# brain2_v12.net
KiCad netlist of a schematic drawn in EAGLE
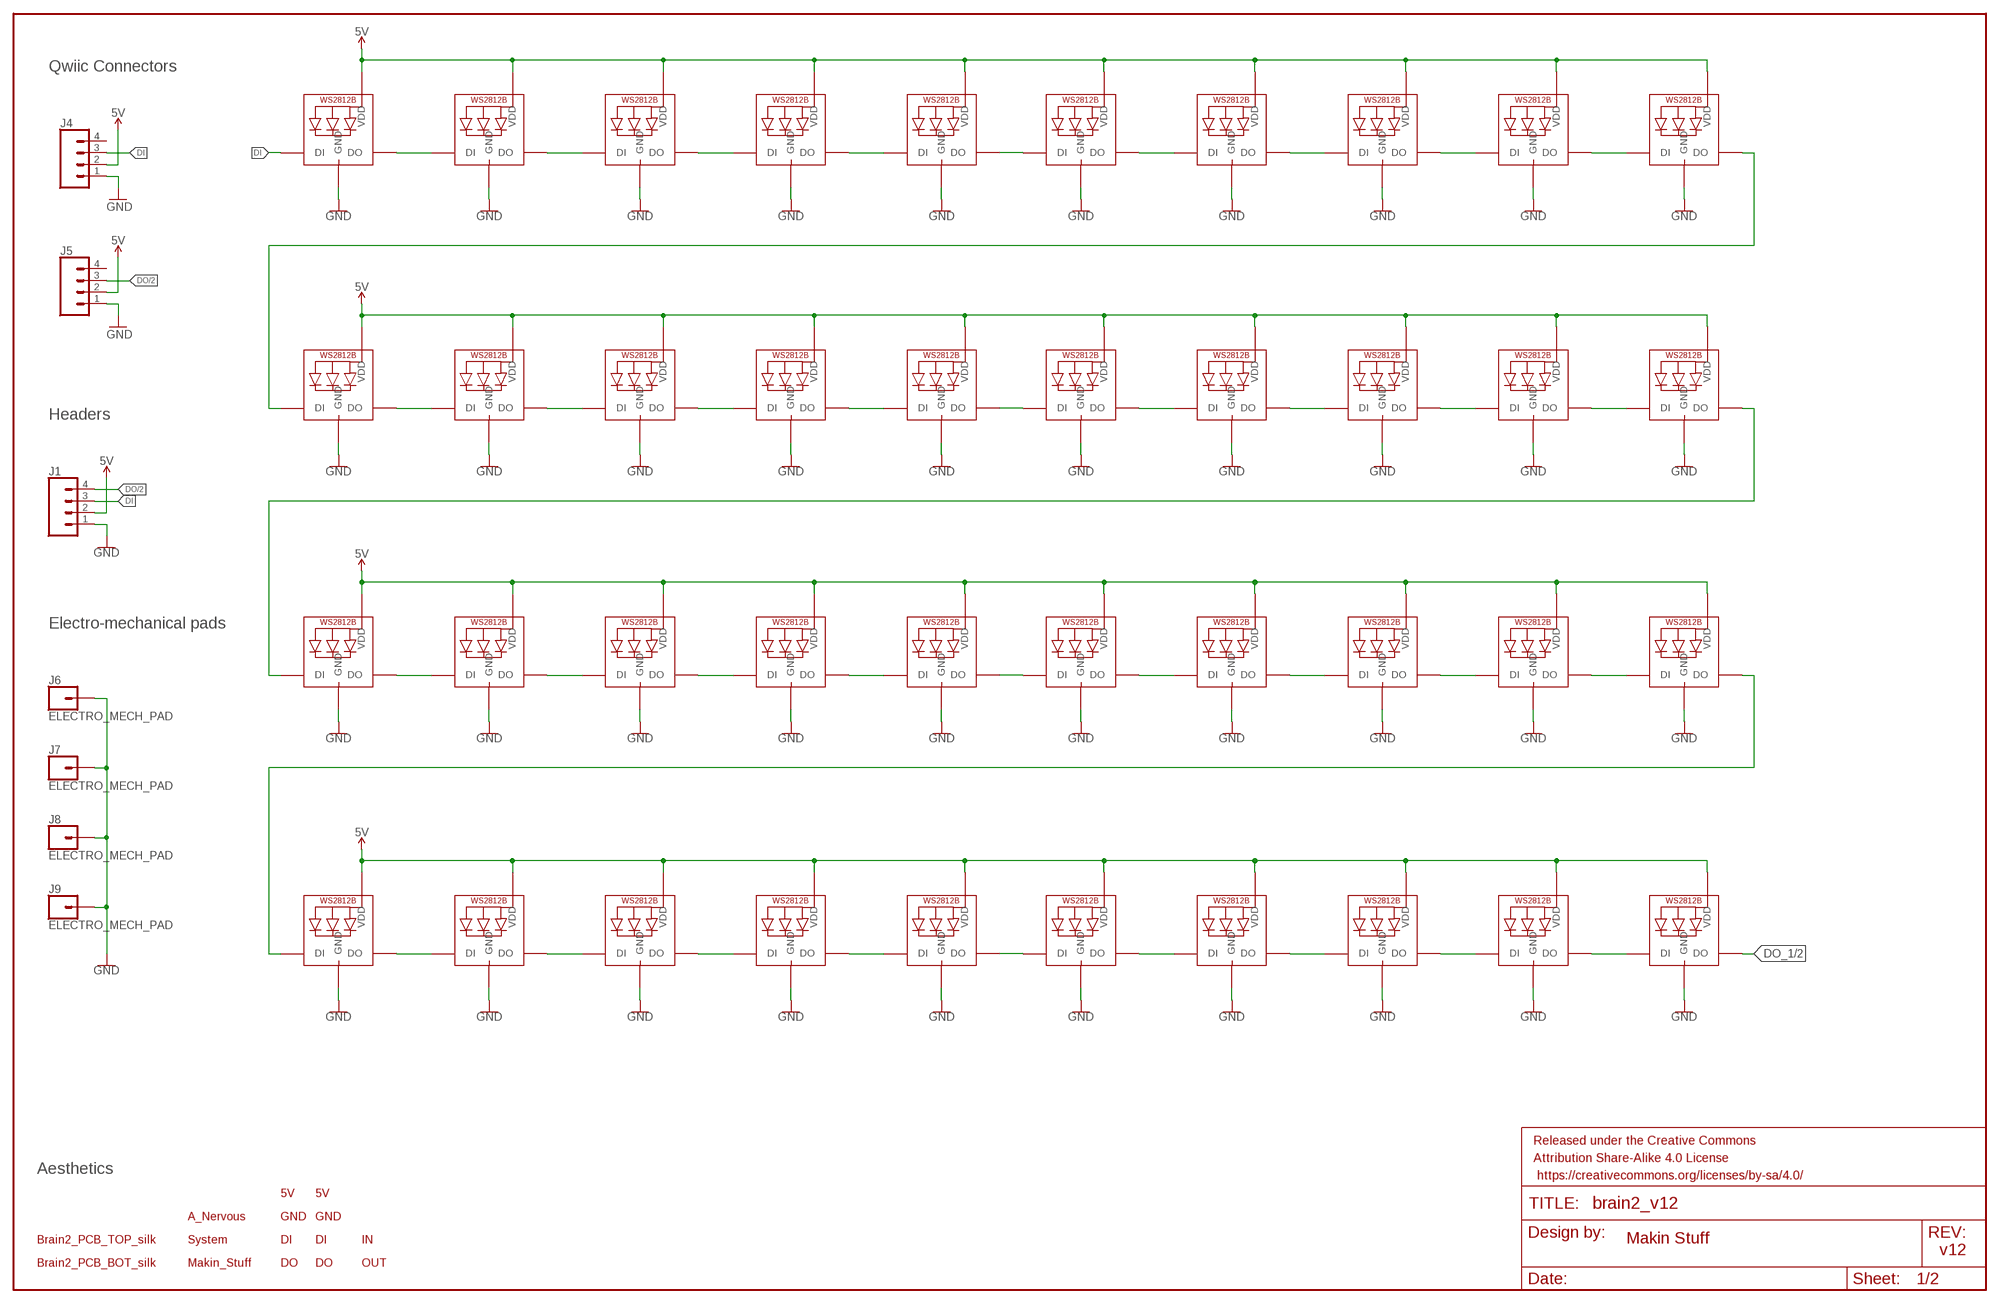
[diagram p0: schematic, sheet 1]
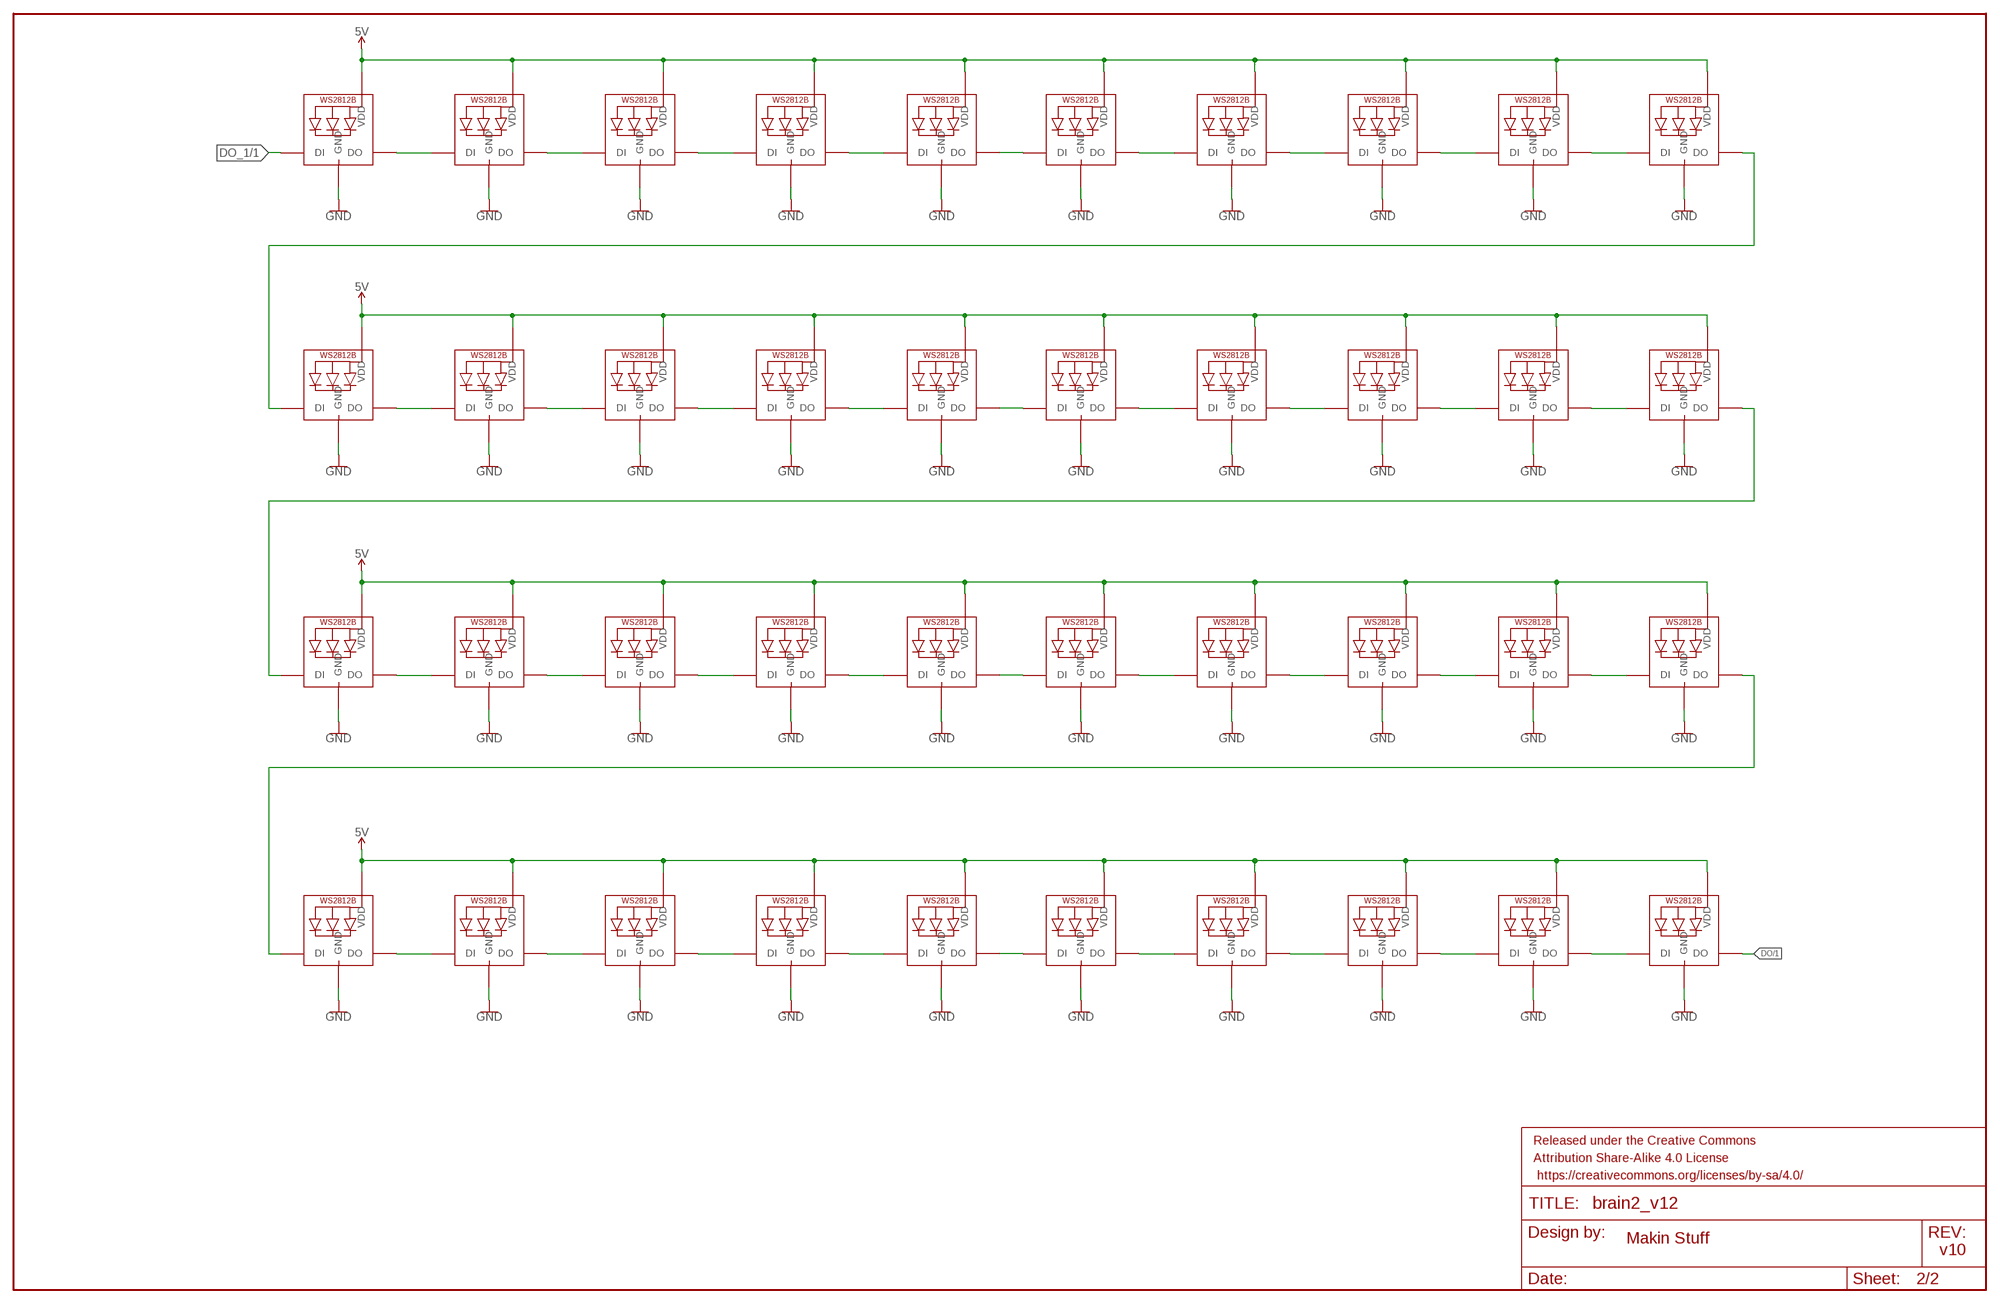
[diagram p1: schematic, sheet 2]

(export (version "E")
  (design (tool "Eeschema 10.0.6"))
  (components
    (comp (ref "FRAME2")
      (value "FRAME-LEDGER")
      (footprint "eagle-import:CREATIVE_COMMONS")
      (libsource (lib "eagle-import") (part "FRAME-LEDGER"))
    )
    (comp (ref "J1")
      (value "CONN_041X04_NO_SILK_NO_POP")
      (footprint "eagle-import:1X04_NO_SILK")
      (libsource (lib "eagle-import") (part "CONN_041X04_NO_SILK_NO_POP"))
    )
    (comp (ref "J4")
      (value "CONN_04SMD3")
      (footprint "eagle-import:JST04_1MM_RA")
      (libsource (lib "eagle-import") (part "CONN_04SMD3"))
    )
    (comp (ref "J5")
      (value "CONN_04SMD3")
      (footprint "eagle-import:JST04_1MM_RA")
      (libsource (lib "eagle-import") (part "CONN_04SMD3"))
    )
    (comp (ref "J6")
      (value "ELECTRO_MECH_PAD")
      (footprint "eagle-import:5X3_SOLDER_PAD")
      (libsource (lib "eagle-import") (part "ELECTRO_MECH_PAD"))
    )
    (comp (ref "J7")
      (value "ELECTRO_MECH_PAD")
      (footprint "eagle-import:5X3_SOLDER_PAD")
      (libsource (lib "eagle-import") (part "ELECTRO_MECH_PAD"))
    )
    (comp (ref "J8")
      (value "ELECTRO_MECH_PAD")
      (footprint "eagle-import:5X3_SOLDER_PAD")
      (libsource (lib "eagle-import") (part "ELECTRO_MECH_PAD"))
    )
    (comp (ref "J9")
      (value "ELECTRO_MECH_PAD")
      (footprint "eagle-import:5X3_SOLDER_PAD")
      (libsource (lib "eagle-import") (part "ELECTRO_MECH_PAD"))
    )
    (comp (ref "LED1")
      (value "3.5X3.5_RGB_LED3.5X3.5")
      (footprint "eagle-import:3.5X3.5_RGB_LED")
      (libsource (lib "eagle-import") (part "3.5X3.5_RGB_LED3.5X3.5"))
    )
    (comp (ref "LED2")
      (value "3.5X3.5_RGB_LED3.5X3.5")
      (footprint "eagle-import:3.5X3.5_RGB_LED")
      (libsource (lib "eagle-import") (part "3.5X3.5_RGB_LED3.5X3.5"))
    )
    (comp (ref "LED3")
      (value "3.5X3.5_RGB_LED3.5X3.5")
      (footprint "eagle-import:3.5X3.5_RGB_LED")
      (libsource (lib "eagle-import") (part "3.5X3.5_RGB_LED3.5X3.5"))
    )
    (comp (ref "LED4")
      (value "3.5X3.5_RGB_LED3.5X3.5")
      (footprint "eagle-import:3.5X3.5_RGB_LED")
      (libsource (lib "eagle-import") (part "3.5X3.5_RGB_LED3.5X3.5"))
    )
    (comp (ref "LED5")
      (value "3.5X3.5_RGB_LED3.5X3.5")
      (footprint "eagle-import:3.5X3.5_RGB_LED")
      (libsource (lib "eagle-import") (part "3.5X3.5_RGB_LED3.5X3.5"))
    )
    (comp (ref "LED6")
      (value "3.5X3.5_RGB_LED3.5X3.5")
      (footprint "eagle-import:3.5X3.5_RGB_LED")
      (libsource (lib "eagle-import") (part "3.5X3.5_RGB_LED3.5X3.5"))
    )
    (comp (ref "LED7")
      (value "3.5X3.5_RGB_LED3.5X3.5")
      (footprint "eagle-import:3.5X3.5_RGB_LED")
      (libsource (lib "eagle-import") (part "3.5X3.5_RGB_LED3.5X3.5"))
    )
    (comp (ref "LED8")
      (value "3.5X3.5_RGB_LED3.5X3.5")
      (footprint "eagle-import:3.5X3.5_RGB_LED")
      (libsource (lib "eagle-import") (part "3.5X3.5_RGB_LED3.5X3.5"))
    )
    (comp (ref "LED9")
      (value "3.5X3.5_RGB_LED3.5X3.5")
      (footprint "eagle-import:3.5X3.5_RGB_LED")
      (libsource (lib "eagle-import") (part "3.5X3.5_RGB_LED3.5X3.5"))
    )
    (comp (ref "LED10")
      (value "3.5X3.5_RGB_LED3.5X3.5")
      (footprint "eagle-import:3.5X3.5_RGB_LED")
      (libsource (lib "eagle-import") (part "3.5X3.5_RGB_LED3.5X3.5"))
    )
    (comp (ref "LED11")
      (value "3.5X3.5_RGB_LED3.5X3.5")
      (footprint "eagle-import:3.5X3.5_RGB_LED")
      (libsource (lib "eagle-import") (part "3.5X3.5_RGB_LED3.5X3.5"))
    )
    (comp (ref "LED12")
      (value "3.5X3.5_RGB_LED3.5X3.5")
      (footprint "eagle-import:3.5X3.5_RGB_LED")
      (libsource (lib "eagle-import") (part "3.5X3.5_RGB_LED3.5X3.5"))
    )
    (comp (ref "LED13")
      (value "3.5X3.5_RGB_LED3.5X3.5")
      (footprint "eagle-import:3.5X3.5_RGB_LED")
      (libsource (lib "eagle-import") (part "3.5X3.5_RGB_LED3.5X3.5"))
    )
    (comp (ref "LED14")
      (value "3.5X3.5_RGB_LED3.5X3.5")
      (footprint "eagle-import:3.5X3.5_RGB_LED")
      (libsource (lib "eagle-import") (part "3.5X3.5_RGB_LED3.5X3.5"))
    )
    (comp (ref "LED15")
      (value "3.5X3.5_RGB_LED3.5X3.5")
      (footprint "eagle-import:3.5X3.5_RGB_LED")
      (libsource (lib "eagle-import") (part "3.5X3.5_RGB_LED3.5X3.5"))
    )
    (comp (ref "LED16")
      (value "3.5X3.5_RGB_LED3.5X3.5")
      (footprint "eagle-import:3.5X3.5_RGB_LED")
      (libsource (lib "eagle-import") (part "3.5X3.5_RGB_LED3.5X3.5"))
    )
    (comp (ref "LED17")
      (value "3.5X3.5_RGB_LED3.5X3.5")
      (footprint "eagle-import:3.5X3.5_RGB_LED")
      (libsource (lib "eagle-import") (part "3.5X3.5_RGB_LED3.5X3.5"))
    )
    (comp (ref "LED18")
      (value "3.5X3.5_RGB_LED3.5X3.5")
      (footprint "eagle-import:3.5X3.5_RGB_LED")
      (libsource (lib "eagle-import") (part "3.5X3.5_RGB_LED3.5X3.5"))
    )
    (comp (ref "LED19")
      (value "3.5X3.5_RGB_LED3.5X3.5")
      (footprint "eagle-import:3.5X3.5_RGB_LED")
      (libsource (lib "eagle-import") (part "3.5X3.5_RGB_LED3.5X3.5"))
    )
    (comp (ref "LED20")
      (value "3.5X3.5_RGB_LED3.5X3.5")
      (footprint "eagle-import:3.5X3.5_RGB_LED")
      (libsource (lib "eagle-import") (part "3.5X3.5_RGB_LED3.5X3.5"))
    )
    (comp (ref "LED21")
      (value "3.5X3.5_RGB_LED3.5X3.5")
      (footprint "eagle-import:3.5X3.5_RGB_LED")
      (libsource (lib "eagle-import") (part "3.5X3.5_RGB_LED3.5X3.5"))
    )
    (comp (ref "LED22")
      (value "3.5X3.5_RGB_LED3.5X3.5")
      (footprint "eagle-import:3.5X3.5_RGB_LED")
      (libsource (lib "eagle-import") (part "3.5X3.5_RGB_LED3.5X3.5"))
    )
    (comp (ref "LED23")
      (value "3.5X3.5_RGB_LED3.5X3.5")
      (footprint "eagle-import:3.5X3.5_RGB_LED")
      (libsource (lib "eagle-import") (part "3.5X3.5_RGB_LED3.5X3.5"))
    )
    (comp (ref "LED24")
      (value "3.5X3.5_RGB_LED3.5X3.5")
      (footprint "eagle-import:3.5X3.5_RGB_LED")
      (libsource (lib "eagle-import") (part "3.5X3.5_RGB_LED3.5X3.5"))
    )
    (comp (ref "LED25")
      (value "3.5X3.5_RGB_LED3.5X3.5")
      (footprint "eagle-import:3.5X3.5_RGB_LED")
      (libsource (lib "eagle-import") (part "3.5X3.5_RGB_LED3.5X3.5"))
    )
    (comp (ref "LED26")
      (value "3.5X3.5_RGB_LED3.5X3.5")
      (footprint "eagle-import:3.5X3.5_RGB_LED")
      (libsource (lib "eagle-import") (part "3.5X3.5_RGB_LED3.5X3.5"))
    )
    (comp (ref "LED27")
      (value "3.5X3.5_RGB_LED3.5X3.5")
      (footprint "eagle-import:3.5X3.5_RGB_LED")
      (libsource (lib "eagle-import") (part "3.5X3.5_RGB_LED3.5X3.5"))
    )
    (comp (ref "LED28")
      (value "3.5X3.5_RGB_LED3.5X3.5")
      (footprint "eagle-import:3.5X3.5_RGB_LED")
      (libsource (lib "eagle-import") (part "3.5X3.5_RGB_LED3.5X3.5"))
    )
    (comp (ref "LED29")
      (value "3.5X3.5_RGB_LED3.5X3.5")
      (footprint "eagle-import:3.5X3.5_RGB_LED")
      (libsource (lib "eagle-import") (part "3.5X3.5_RGB_LED3.5X3.5"))
    )
    (comp (ref "LED30")
      (value "3.5X3.5_RGB_LED3.5X3.5")
      (footprint "eagle-import:3.5X3.5_RGB_LED")
      (libsource (lib "eagle-import") (part "3.5X3.5_RGB_LED3.5X3.5"))
    )
    (comp (ref "LED31")
      (value "3.5X3.5_RGB_LED3.5X3.5")
      (footprint "eagle-import:3.5X3.5_RGB_LED")
      (libsource (lib "eagle-import") (part "3.5X3.5_RGB_LED3.5X3.5"))
    )
    (comp (ref "LED32")
      (value "3.5X3.5_RGB_LED3.5X3.5")
      (footprint "eagle-import:3.5X3.5_RGB_LED")
      (libsource (lib "eagle-import") (part "3.5X3.5_RGB_LED3.5X3.5"))
    )
    (comp (ref "LED33")
      (value "3.5X3.5_RGB_LED3.5X3.5")
      (footprint "eagle-import:3.5X3.5_RGB_LED")
      (libsource (lib "eagle-import") (part "3.5X3.5_RGB_LED3.5X3.5"))
    )
    (comp (ref "LED34")
      (value "3.5X3.5_RGB_LED3.5X3.5")
      (footprint "eagle-import:3.5X3.5_RGB_LED")
      (libsource (lib "eagle-import") (part "3.5X3.5_RGB_LED3.5X3.5"))
    )
    (comp (ref "LED35")
      (value "3.5X3.5_RGB_LED3.5X3.5")
      (footprint "eagle-import:3.5X3.5_RGB_LED")
      (libsource (lib "eagle-import") (part "3.5X3.5_RGB_LED3.5X3.5"))
    )
    (comp (ref "LED36")
      (value "3.5X3.5_RGB_LED3.5X3.5")
      (footprint "eagle-import:3.5X3.5_RGB_LED")
      (libsource (lib "eagle-import") (part "3.5X3.5_RGB_LED3.5X3.5"))
    )
    (comp (ref "LED37")
      (value "3.5X3.5_RGB_LED3.5X3.5")
      (footprint "eagle-import:3.5X3.5_RGB_LED")
      (libsource (lib "eagle-import") (part "3.5X3.5_RGB_LED3.5X3.5"))
    )
    (comp (ref "LED38")
      (value "3.5X3.5_RGB_LED3.5X3.5")
      (footprint "eagle-import:3.5X3.5_RGB_LED")
      (libsource (lib "eagle-import") (part "3.5X3.5_RGB_LED3.5X3.5"))
    )
    (comp (ref "LED39")
      (value "3.5X3.5_RGB_LED3.5X3.5")
      (footprint "eagle-import:3.5X3.5_RGB_LED")
      (libsource (lib "eagle-import") (part "3.5X3.5_RGB_LED3.5X3.5"))
    )
    (comp (ref "LED40")
      (value "3.5X3.5_RGB_LED3.5X3.5")
      (footprint "eagle-import:3.5X3.5_RGB_LED")
      (libsource (lib "eagle-import") (part "3.5X3.5_RGB_LED3.5X3.5"))
    )
    (comp (ref "U$1")
      (value "A_NERVOUS0")
      (footprint "eagle-import:A_NERVOUS0")
      (libsource (lib "eagle-import") (part "A_NERVOUS0"))
    )
    (comp (ref "U$2")
      (value "SYSTEM1")
      (footprint "eagle-import:SYSTEM1")
      (libsource (lib "eagle-import") (part "SYSTEM1"))
    )
    (comp (ref "U$3")
      (value "MAKIN_STUFF2")
      (footprint "eagle-import:MAKIN_STUFF2")
      (libsource (lib "eagle-import") (part "MAKIN_STUFF2"))
    )
    (comp (ref "U$4")
      (value "5V1")
      (footprint "eagle-import:5V1")
      (libsource (lib "eagle-import") (part "5V1"))
    )
    (comp (ref "U$5")
      (value "5V1")
      (footprint "eagle-import:5V1")
      (libsource (lib "eagle-import") (part "5V1"))
    )
    (comp (ref "U$6")
      (value "GND0")
      (footprint "eagle-import:GND0")
      (libsource (lib "eagle-import") (part "GND0"))
    )
    (comp (ref "U$7")
      (value "GND0")
      (footprint "eagle-import:GND0")
      (libsource (lib "eagle-import") (part "GND0"))
    )
    (comp (ref "U$8")
      (value "DI0")
      (footprint "eagle-import:DI0")
      (libsource (lib "eagle-import") (part "DI0"))
    )
    (comp (ref "U$9")
      (value "DI0")
      (footprint "eagle-import:DI0")
      (libsource (lib "eagle-import") (part "DI0"))
    )
    (comp (ref "U$10")
      (value "DO3")
      (footprint "eagle-import:DO3")
      (libsource (lib "eagle-import") (part "DO3"))
    )
    (comp (ref "U$11")
      (value "DO3")
      (footprint "eagle-import:DO3")
      (libsource (lib "eagle-import") (part "DO3"))
    )
    (comp (ref "U$12")
      (value "IN0")
      (footprint "eagle-import:IN0")
      (libsource (lib "eagle-import") (part "IN0"))
    )
    (comp (ref "U$13")
      (value "OUT1")
      (footprint "eagle-import:OUT1")
      (libsource (lib "eagle-import") (part "OUT1"))
    )
    (comp (ref "U$14")
      (value "BRAIN2_PCB_TOP_SILK")
      (footprint "eagle-import:BRAIN2_PCB_TOP_SILK")
      (libsource (lib "eagle-import") (part "BRAIN2_PCB_TOP_SILK"))
    )
    (comp (ref "U$15")
      (value "BRAIN2_PCB_BOT_SILK")
      (footprint "eagle-import:BRAIN2_PCB_BOT_SILK")
      (libsource (lib "eagle-import") (part "BRAIN2_PCB_BOT_SILK"))
    )
    (comp (ref "FRAME1")
      (value "FRAME-LEDGER")
      (footprint "eagle-import:CREATIVE_COMMONS")
      (libsource (lib "eagle-import") (part "FRAME-LEDGER"))
    )
    (comp (ref "FRAME3")
      (value "FRAME-LEDGER")
      (footprint "eagle-import:CREATIVE_COMMONS")
      (libsource (lib "eagle-import") (part "FRAME-LEDGER"))
    )
    (comp (ref "LED41")
      (value "3.5X3.5_RGB_LED3.5X3.5")
      (footprint "eagle-import:3.5X3.5_RGB_LED")
      (libsource (lib "eagle-import") (part "3.5X3.5_RGB_LED3.5X3.5"))
    )
    (comp (ref "LED42")
      (value "3.5X3.5_RGB_LED3.5X3.5")
      (footprint "eagle-import:3.5X3.5_RGB_LED")
      (libsource (lib "eagle-import") (part "3.5X3.5_RGB_LED3.5X3.5"))
    )
    (comp (ref "LED43")
      (value "3.5X3.5_RGB_LED3.5X3.5")
      (footprint "eagle-import:3.5X3.5_RGB_LED")
      (libsource (lib "eagle-import") (part "3.5X3.5_RGB_LED3.5X3.5"))
    )
    (comp (ref "LED44")
      (value "3.5X3.5_RGB_LED3.5X3.5")
      (footprint "eagle-import:3.5X3.5_RGB_LED")
      (libsource (lib "eagle-import") (part "3.5X3.5_RGB_LED3.5X3.5"))
    )
    (comp (ref "LED45")
      (value "3.5X3.5_RGB_LED3.5X3.5")
      (footprint "eagle-import:3.5X3.5_RGB_LED")
      (libsource (lib "eagle-import") (part "3.5X3.5_RGB_LED3.5X3.5"))
    )
    (comp (ref "LED46")
      (value "3.5X3.5_RGB_LED3.5X3.5")
      (footprint "eagle-import:3.5X3.5_RGB_LED")
      (libsource (lib "eagle-import") (part "3.5X3.5_RGB_LED3.5X3.5"))
    )
    (comp (ref "LED47")
      (value "3.5X3.5_RGB_LED3.5X3.5")
      (footprint "eagle-import:3.5X3.5_RGB_LED")
      (libsource (lib "eagle-import") (part "3.5X3.5_RGB_LED3.5X3.5"))
    )
    (comp (ref "LED48")
      (value "3.5X3.5_RGB_LED3.5X3.5")
      (footprint "eagle-import:3.5X3.5_RGB_LED")
      (libsource (lib "eagle-import") (part "3.5X3.5_RGB_LED3.5X3.5"))
    )
    (comp (ref "LED49")
      (value "3.5X3.5_RGB_LED3.5X3.5")
      (footprint "eagle-import:3.5X3.5_RGB_LED")
      (libsource (lib "eagle-import") (part "3.5X3.5_RGB_LED3.5X3.5"))
    )
    (comp (ref "LED50")
      (value "3.5X3.5_RGB_LED3.5X3.5")
      (footprint "eagle-import:3.5X3.5_RGB_LED")
      (libsource (lib "eagle-import") (part "3.5X3.5_RGB_LED3.5X3.5"))
    )
    (comp (ref "LED51")
      (value "3.5X3.5_RGB_LED3.5X3.5")
      (footprint "eagle-import:3.5X3.5_RGB_LED")
      (libsource (lib "eagle-import") (part "3.5X3.5_RGB_LED3.5X3.5"))
    )
    (comp (ref "LED52")
      (value "3.5X3.5_RGB_LED3.5X3.5")
      (footprint "eagle-import:3.5X3.5_RGB_LED")
      (libsource (lib "eagle-import") (part "3.5X3.5_RGB_LED3.5X3.5"))
    )
    (comp (ref "LED53")
      (value "3.5X3.5_RGB_LED3.5X3.5")
      (footprint "eagle-import:3.5X3.5_RGB_LED")
      (libsource (lib "eagle-import") (part "3.5X3.5_RGB_LED3.5X3.5"))
    )
    (comp (ref "LED54")
      (value "3.5X3.5_RGB_LED3.5X3.5")
      (footprint "eagle-import:3.5X3.5_RGB_LED")
      (libsource (lib "eagle-import") (part "3.5X3.5_RGB_LED3.5X3.5"))
    )
    (comp (ref "LED55")
      (value "3.5X3.5_RGB_LED3.5X3.5")
      (footprint "eagle-import:3.5X3.5_RGB_LED")
      (libsource (lib "eagle-import") (part "3.5X3.5_RGB_LED3.5X3.5"))
    )
    (comp (ref "LED56")
      (value "3.5X3.5_RGB_LED3.5X3.5")
      (footprint "eagle-import:3.5X3.5_RGB_LED")
      (libsource (lib "eagle-import") (part "3.5X3.5_RGB_LED3.5X3.5"))
    )
    (comp (ref "LED57")
      (value "3.5X3.5_RGB_LED3.5X3.5")
      (footprint "eagle-import:3.5X3.5_RGB_LED")
      (libsource (lib "eagle-import") (part "3.5X3.5_RGB_LED3.5X3.5"))
    )
    (comp (ref "LED58")
      (value "3.5X3.5_RGB_LED3.5X3.5")
      (footprint "eagle-import:3.5X3.5_RGB_LED")
      (libsource (lib "eagle-import") (part "3.5X3.5_RGB_LED3.5X3.5"))
    )
    (comp (ref "LED59")
      (value "3.5X3.5_RGB_LED3.5X3.5")
      (footprint "eagle-import:3.5X3.5_RGB_LED")
      (libsource (lib "eagle-import") (part "3.5X3.5_RGB_LED3.5X3.5"))
    )
    (comp (ref "LED60")
      (value "3.5X3.5_RGB_LED3.5X3.5")
      (footprint "eagle-import:3.5X3.5_RGB_LED")
      (libsource (lib "eagle-import") (part "3.5X3.5_RGB_LED3.5X3.5"))
    )
    (comp (ref "LED61")
      (value "3.5X3.5_RGB_LED3.5X3.5")
      (footprint "eagle-import:3.5X3.5_RGB_LED")
      (libsource (lib "eagle-import") (part "3.5X3.5_RGB_LED3.5X3.5"))
    )
    (comp (ref "LED62")
      (value "3.5X3.5_RGB_LED3.5X3.5")
      (footprint "eagle-import:3.5X3.5_RGB_LED")
      (libsource (lib "eagle-import") (part "3.5X3.5_RGB_LED3.5X3.5"))
    )
    (comp (ref "LED63")
      (value "3.5X3.5_RGB_LED3.5X3.5")
      (footprint "eagle-import:3.5X3.5_RGB_LED")
      (libsource (lib "eagle-import") (part "3.5X3.5_RGB_LED3.5X3.5"))
    )
    (comp (ref "LED64")
      (value "3.5X3.5_RGB_LED3.5X3.5")
      (footprint "eagle-import:3.5X3.5_RGB_LED")
      (libsource (lib "eagle-import") (part "3.5X3.5_RGB_LED3.5X3.5"))
    )
    (comp (ref "LED65")
      (value "3.5X3.5_RGB_LED3.5X3.5")
      (footprint "eagle-import:3.5X3.5_RGB_LED")
      (libsource (lib "eagle-import") (part "3.5X3.5_RGB_LED3.5X3.5"))
    )
    (comp (ref "LED66")
      (value "3.5X3.5_RGB_LED3.5X3.5")
      (footprint "eagle-import:3.5X3.5_RGB_LED")
      (libsource (lib "eagle-import") (part "3.5X3.5_RGB_LED3.5X3.5"))
    )
    (comp (ref "LED67")
      (value "3.5X3.5_RGB_LED3.5X3.5")
      (footprint "eagle-import:3.5X3.5_RGB_LED")
      (libsource (lib "eagle-import") (part "3.5X3.5_RGB_LED3.5X3.5"))
    )
    (comp (ref "LED68")
      (value "3.5X3.5_RGB_LED3.5X3.5")
      (footprint "eagle-import:3.5X3.5_RGB_LED")
      (libsource (lib "eagle-import") (part "3.5X3.5_RGB_LED3.5X3.5"))
    )
    (comp (ref "LED69")
      (value "3.5X3.5_RGB_LED3.5X3.5")
      (footprint "eagle-import:3.5X3.5_RGB_LED")
      (libsource (lib "eagle-import") (part "3.5X3.5_RGB_LED3.5X3.5"))
    )
    (comp (ref "LED70")
      (value "3.5X3.5_RGB_LED3.5X3.5")
      (footprint "eagle-import:3.5X3.5_RGB_LED")
      (libsource (lib "eagle-import") (part "3.5X3.5_RGB_LED3.5X3.5"))
    )
    (comp (ref "LED71")
      (value "3.5X3.5_RGB_LED3.5X3.5")
      (footprint "eagle-import:3.5X3.5_RGB_LED")
      (libsource (lib "eagle-import") (part "3.5X3.5_RGB_LED3.5X3.5"))
    )
    (comp (ref "LED72")
      (value "3.5X3.5_RGB_LED3.5X3.5")
      (footprint "eagle-import:3.5X3.5_RGB_LED")
      (libsource (lib "eagle-import") (part "3.5X3.5_RGB_LED3.5X3.5"))
    )
    (comp (ref "LED73")
      (value "3.5X3.5_RGB_LED3.5X3.5")
      (footprint "eagle-import:3.5X3.5_RGB_LED")
      (libsource (lib "eagle-import") (part "3.5X3.5_RGB_LED3.5X3.5"))
    )
    (comp (ref "LED74")
      (value "3.5X3.5_RGB_LED3.5X3.5")
      (footprint "eagle-import:3.5X3.5_RGB_LED")
      (libsource (lib "eagle-import") (part "3.5X3.5_RGB_LED3.5X3.5"))
    )
    (comp (ref "LED75")
      (value "3.5X3.5_RGB_LED3.5X3.5")
      (footprint "eagle-import:3.5X3.5_RGB_LED")
      (libsource (lib "eagle-import") (part "3.5X3.5_RGB_LED3.5X3.5"))
    )
    (comp (ref "LED76")
      (value "3.5X3.5_RGB_LED3.5X3.5")
      (footprint "eagle-import:3.5X3.5_RGB_LED")
      (libsource (lib "eagle-import") (part "3.5X3.5_RGB_LED3.5X3.5"))
    )
    (comp (ref "LED77")
      (value "3.5X3.5_RGB_LED3.5X3.5")
      (footprint "eagle-import:3.5X3.5_RGB_LED")
      (libsource (lib "eagle-import") (part "3.5X3.5_RGB_LED3.5X3.5"))
    )
    (comp (ref "LED78")
      (value "3.5X3.5_RGB_LED3.5X3.5")
      (footprint "eagle-import:3.5X3.5_RGB_LED")
      (libsource (lib "eagle-import") (part "3.5X3.5_RGB_LED3.5X3.5"))
    )
    (comp (ref "LED79")
      (value "3.5X3.5_RGB_LED3.5X3.5")
      (footprint "eagle-import:3.5X3.5_RGB_LED")
      (libsource (lib "eagle-import") (part "3.5X3.5_RGB_LED3.5X3.5"))
    )
    (comp (ref "LED80")
      (value "3.5X3.5_RGB_LED3.5X3.5")
      (footprint "eagle-import:3.5X3.5_RGB_LED")
      (libsource (lib "eagle-import") (part "3.5X3.5_RGB_LED3.5X3.5"))
    )
  )
  (nets
    (net (code "1") (name "5V") (class "Default")
      (node (ref "J1") (pin "2") (pinfunction "2_2") (pintype "passive"))
      (node (ref "J4") (pin "2") (pinfunction "2_2") (pintype "passive"))
      (node (ref "J5") (pin "2") (pinfunction "2_2") (pintype "passive"))
      (node (ref "LED1") (pin "4") (pinfunction "VDD_4") (pintype "power_in"))
      (node (ref "LED10") (pin "4") (pinfunction "VDD_4") (pintype "power_in"))
      (node (ref "LED11") (pin "4") (pinfunction "VDD_4") (pintype "power_in"))
      (node (ref "LED12") (pin "4") (pinfunction "VDD_4") (pintype "power_in"))
      (node (ref "LED13") (pin "4") (pinfunction "VDD_4") (pintype "power_in"))
      (node (ref "LED14") (pin "4") (pinfunction "VDD_4") (pintype "power_in"))
      (node (ref "LED15") (pin "4") (pinfunction "VDD_4") (pintype "power_in"))
      (node (ref "LED16") (pin "4") (pinfunction "VDD_4") (pintype "power_in"))
      (node (ref "LED17") (pin "4") (pinfunction "VDD_4") (pintype "power_in"))
      (node (ref "LED18") (pin "4") (pinfunction "VDD_4") (pintype "power_in"))
      (node (ref "LED19") (pin "4") (pinfunction "VDD_4") (pintype "power_in"))
      (node (ref "LED2") (pin "4") (pinfunction "VDD_4") (pintype "power_in"))
      (node (ref "LED20") (pin "4") (pinfunction "VDD_4") (pintype "power_in"))
      (node (ref "LED21") (pin "4") (pinfunction "VDD_4") (pintype "power_in"))
      (node (ref "LED22") (pin "4") (pinfunction "VDD_4") (pintype "power_in"))
      (node (ref "LED23") (pin "4") (pinfunction "VDD_4") (pintype "power_in"))
      (node (ref "LED24") (pin "4") (pinfunction "VDD_4") (pintype "power_in"))
      (node (ref "LED25") (pin "4") (pinfunction "VDD_4") (pintype "power_in"))
      (node (ref "LED26") (pin "4") (pinfunction "VDD_4") (pintype "power_in"))
      (node (ref "LED27") (pin "4") (pinfunction "VDD_4") (pintype "power_in"))
      (node (ref "LED28") (pin "4") (pinfunction "VDD_4") (pintype "power_in"))
      (node (ref "LED29") (pin "4") (pinfunction "VDD_4") (pintype "power_in"))
      (node (ref "LED3") (pin "4") (pinfunction "VDD_4") (pintype "power_in"))
      (node (ref "LED30") (pin "4") (pinfunction "VDD_4") (pintype "power_in"))
      (node (ref "LED31") (pin "4") (pinfunction "VDD_4") (pintype "power_in"))
      (node (ref "LED32") (pin "4") (pinfunction "VDD_4") (pintype "power_in"))
      (node (ref "LED33") (pin "4") (pinfunction "VDD_4") (pintype "power_in"))
      (node (ref "LED34") (pin "4") (pinfunction "VDD_4") (pintype "power_in"))
      (node (ref "LED35") (pin "4") (pinfunction "VDD_4") (pintype "power_in"))
      (node (ref "LED36") (pin "4") (pinfunction "VDD_4") (pintype "power_in"))
      (node (ref "LED37") (pin "4") (pinfunction "VDD_4") (pintype "power_in"))
      (node (ref "LED38") (pin "4") (pinfunction "VDD_4") (pintype "power_in"))
      (node (ref "LED39") (pin "4") (pinfunction "VDD_4") (pintype "power_in"))
      (node (ref "LED4") (pin "4") (pinfunction "VDD_4") (pintype "power_in"))
      (node (ref "LED40") (pin "4") (pinfunction "VDD_4") (pintype "power_in"))
      (node (ref "LED41") (pin "4") (pinfunction "VDD_4") (pintype "power_in"))
      (node (ref "LED42") (pin "4") (pinfunction "VDD_4") (pintype "power_in"))
      (node (ref "LED43") (pin "4") (pinfunction "VDD_4") (pintype "power_in"))
      (node (ref "LED44") (pin "4") (pinfunction "VDD_4") (pintype "power_in"))
      (node (ref "LED45") (pin "4") (pinfunction "VDD_4") (pintype "power_in"))
      (node (ref "LED46") (pin "4") (pinfunction "VDD_4") (pintype "power_in"))
      (node (ref "LED47") (pin "4") (pinfunction "VDD_4") (pintype "power_in"))
      (node (ref "LED48") (pin "4") (pinfunction "VDD_4") (pintype "power_in"))
      (node (ref "LED49") (pin "4") (pinfunction "VDD_4") (pintype "power_in"))
      (node (ref "LED5") (pin "4") (pinfunction "VDD_4") (pintype "power_in"))
      (node (ref "LED50") (pin "4") (pinfunction "VDD_4") (pintype "power_in"))
      (node (ref "LED51") (pin "4") (pinfunction "VDD_4") (pintype "power_in"))
      (node (ref "LED52") (pin "4") (pinfunction "VDD_4") (pintype "power_in"))
      (node (ref "LED53") (pin "4") (pinfunction "VDD_4") (pintype "power_in"))
      (node (ref "LED54") (pin "4") (pinfunction "VDD_4") (pintype "power_in"))
      (node (ref "LED55") (pin "4") (pinfunction "VDD_4") (pintype "power_in"))
      (node (ref "LED56") (pin "4") (pinfunction "VDD_4") (pintype "power_in"))
      (node (ref "LED57") (pin "4") (pinfunction "VDD_4") (pintype "power_in"))
      (node (ref "LED58") (pin "4") (pinfunction "VDD_4") (pintype "power_in"))
      (node (ref "LED59") (pin "4") (pinfunction "VDD_4") (pintype "power_in"))
      (node (ref "LED6") (pin "4") (pinfunction "VDD_4") (pintype "power_in"))
      (node (ref "LED60") (pin "4") (pinfunction "VDD_4") (pintype "power_in"))
      (node (ref "LED61") (pin "4") (pinfunction "VDD_4") (pintype "power_in"))
      (node (ref "LED62") (pin "4") (pinfunction "VDD_4") (pintype "power_in"))
      (node (ref "LED63") (pin "4") (pinfunction "VDD_4") (pintype "power_in"))
      (node (ref "LED64") (pin "4") (pinfunction "VDD_4") (pintype "power_in"))
      (node (ref "LED65") (pin "4") (pinfunction "VDD_4") (pintype "power_in"))
      (node (ref "LED66") (pin "4") (pinfunction "VDD_4") (pintype "power_in"))
      (node (ref "LED67") (pin "4") (pinfunction "VDD_4") (pintype "power_in"))
      (node (ref "LED68") (pin "4") (pinfunction "VDD_4") (pintype "power_in"))
      (node (ref "LED69") (pin "4") (pinfunction "VDD_4") (pintype "power_in"))
      (node (ref "LED7") (pin "4") (pinfunction "VDD_4") (pintype "power_in"))
      (node (ref "LED70") (pin "4") (pinfunction "VDD_4") (pintype "power_in"))
      (node (ref "LED71") (pin "4") (pinfunction "VDD_4") (pintype "power_in"))
      (node (ref "LED72") (pin "4") (pinfunction "VDD_4") (pintype "power_in"))
      (node (ref "LED73") (pin "4") (pinfunction "VDD_4") (pintype "power_in"))
      (node (ref "LED74") (pin "4") (pinfunction "VDD_4") (pintype "power_in"))
      (node (ref "LED75") (pin "4") (pinfunction "VDD_4") (pintype "power_in"))
      (node (ref "LED76") (pin "4") (pinfunction "VDD_4") (pintype "power_in"))
      (node (ref "LED77") (pin "4") (pinfunction "VDD_4") (pintype "power_in"))
      (node (ref "LED78") (pin "4") (pinfunction "VDD_4") (pintype "power_in"))
      (node (ref "LED79") (pin "4") (pinfunction "VDD_4") (pintype "power_in"))
      (node (ref "LED8") (pin "4") (pinfunction "VDD_4") (pintype "power_in"))
      (node (ref "LED80") (pin "4") (pinfunction "VDD_4") (pintype "power_in"))
      (node (ref "LED9") (pin "4") (pinfunction "VDD_4") (pintype "power_in"))
    )
    (net (code "2") (name "DI") (class "Default")
      (node (ref "J1") (pin "3") (pinfunction "3_3") (pintype "passive"))
      (node (ref "J4") (pin "3") (pinfunction "3_3") (pintype "passive"))
      (node (ref "LED1") (pin "3") (pinfunction "DI_3") (pintype "input"))
    )
    (net (code "3") (name "DO") (class "Default")
      (node (ref "J1") (pin "4") (pinfunction "4_4") (pintype "passive"))
      (node (ref "J5") (pin "3") (pinfunction "3_3") (pintype "passive"))
      (node (ref "LED80") (pin "1") (pinfunction "DO_1") (pintype "output"))
    )
    (net (code "4") (name "DO_1") (class "Default")
      (node (ref "LED40") (pin "1") (pinfunction "DO_1") (pintype "output"))
      (node (ref "LED41") (pin "3") (pinfunction "DI_3") (pintype "input"))
    )
    (net (code "5") (name "GND") (class "Default")
      (node (ref "J1") (pin "1") (pinfunction "1_1") (pintype "passive"))
      (node (ref "J4") (pin "1") (pinfunction "1_1") (pintype "passive"))
      (node (ref "J5") (pin "1") (pinfunction "1_1") (pintype "passive"))
      (node (ref "J6") (pin "P$1") (pinfunction "1_P$1") (pintype "passive"))
      (node (ref "J7") (pin "P$1") (pinfunction "1_P$1") (pintype "passive"))
      (node (ref "J8") (pin "P$1") (pinfunction "1_P$1") (pintype "passive"))
      (node (ref "J9") (pin "P$1") (pinfunction "1_P$1") (pintype "passive"))
      (node (ref "LED1") (pin "2") (pinfunction "GND_2") (pintype "power_in"))
      (node (ref "LED10") (pin "2") (pinfunction "GND_2") (pintype "power_in"))
      (node (ref "LED11") (pin "2") (pinfunction "GND_2") (pintype "power_in"))
      (node (ref "LED12") (pin "2") (pinfunction "GND_2") (pintype "power_in"))
      (node (ref "LED13") (pin "2") (pinfunction "GND_2") (pintype "power_in"))
      (node (ref "LED14") (pin "2") (pinfunction "GND_2") (pintype "power_in"))
      (node (ref "LED15") (pin "2") (pinfunction "GND_2") (pintype "power_in"))
      (node (ref "LED16") (pin "2") (pinfunction "GND_2") (pintype "power_in"))
      (node (ref "LED17") (pin "2") (pinfunction "GND_2") (pintype "power_in"))
      (node (ref "LED18") (pin "2") (pinfunction "GND_2") (pintype "power_in"))
      (node (ref "LED19") (pin "2") (pinfunction "GND_2") (pintype "power_in"))
      (node (ref "LED2") (pin "2") (pinfunction "GND_2") (pintype "power_in"))
      (node (ref "LED20") (pin "2") (pinfunction "GND_2") (pintype "power_in"))
      (node (ref "LED21") (pin "2") (pinfunction "GND_2") (pintype "power_in"))
      (node (ref "LED22") (pin "2") (pinfunction "GND_2") (pintype "power_in"))
      (node (ref "LED23") (pin "2") (pinfunction "GND_2") (pintype "power_in"))
      (node (ref "LED24") (pin "2") (pinfunction "GND_2") (pintype "power_in"))
      (node (ref "LED25") (pin "2") (pinfunction "GND_2") (pintype "power_in"))
      (node (ref "LED26") (pin "2") (pinfunction "GND_2") (pintype "power_in"))
      (node (ref "LED27") (pin "2") (pinfunction "GND_2") (pintype "power_in"))
      (node (ref "LED28") (pin "2") (pinfunction "GND_2") (pintype "power_in"))
      (node (ref "LED29") (pin "2") (pinfunction "GND_2") (pintype "power_in"))
      (node (ref "LED3") (pin "2") (pinfunction "GND_2") (pintype "power_in"))
      (node (ref "LED30") (pin "2") (pinfunction "GND_2") (pintype "power_in"))
      (node (ref "LED31") (pin "2") (pinfunction "GND_2") (pintype "power_in"))
      (node (ref "LED32") (pin "2") (pinfunction "GND_2") (pintype "power_in"))
      (node (ref "LED33") (pin "2") (pinfunction "GND_2") (pintype "power_in"))
      (node (ref "LED34") (pin "2") (pinfunction "GND_2") (pintype "power_in"))
      (node (ref "LED35") (pin "2") (pinfunction "GND_2") (pintype "power_in"))
      (node (ref "LED36") (pin "2") (pinfunction "GND_2") (pintype "power_in"))
      (node (ref "LED37") (pin "2") (pinfunction "GND_2") (pintype "power_in"))
      (node (ref "LED38") (pin "2") (pinfunction "GND_2") (pintype "power_in"))
      (node (ref "LED39") (pin "2") (pinfunction "GND_2") (pintype "power_in"))
      (node (ref "LED4") (pin "2") (pinfunction "GND_2") (pintype "power_in"))
      (node (ref "LED40") (pin "2") (pinfunction "GND_2") (pintype "power_in"))
      (node (ref "LED41") (pin "2") (pinfunction "GND_2") (pintype "power_in"))
      (node (ref "LED42") (pin "2") (pinfunction "GND_2") (pintype "power_in"))
      (node (ref "LED43") (pin "2") (pinfunction "GND_2") (pintype "power_in"))
      (node (ref "LED44") (pin "2") (pinfunction "GND_2") (pintype "power_in"))
      (node (ref "LED45") (pin "2") (pinfunction "GND_2") (pintype "power_in"))
      (node (ref "LED46") (pin "2") (pinfunction "GND_2") (pintype "power_in"))
      (node (ref "LED47") (pin "2") (pinfunction "GND_2") (pintype "power_in"))
      (node (ref "LED48") (pin "2") (pinfunction "GND_2") (pintype "power_in"))
      (node (ref "LED49") (pin "2") (pinfunction "GND_2") (pintype "power_in"))
      (node (ref "LED5") (pin "2") (pinfunction "GND_2") (pintype "power_in"))
      (node (ref "LED50") (pin "2") (pinfunction "GND_2") (pintype "power_in"))
      (node (ref "LED51") (pin "2") (pinfunction "GND_2") (pintype "power_in"))
      (node (ref "LED52") (pin "2") (pinfunction "GND_2") (pintype "power_in"))
      (node (ref "LED53") (pin "2") (pinfunction "GND_2") (pintype "power_in"))
      (node (ref "LED54") (pin "2") (pinfunction "GND_2") (pintype "power_in"))
      (node (ref "LED55") (pin "2") (pinfunction "GND_2") (pintype "power_in"))
      (node (ref "LED56") (pin "2") (pinfunction "GND_2") (pintype "power_in"))
      (node (ref "LED57") (pin "2") (pinfunction "GND_2") (pintype "power_in"))
      (node (ref "LED58") (pin "2") (pinfunction "GND_2") (pintype "power_in"))
      (node (ref "LED59") (pin "2") (pinfunction "GND_2") (pintype "power_in"))
      (node (ref "LED6") (pin "2") (pinfunction "GND_2") (pintype "power_in"))
      (node (ref "LED60") (pin "2") (pinfunction "GND_2") (pintype "power_in"))
      (node (ref "LED61") (pin "2") (pinfunction "GND_2") (pintype "power_in"))
      (node (ref "LED62") (pin "2") (pinfunction "GND_2") (pintype "power_in"))
      (node (ref "LED63") (pin "2") (pinfunction "GND_2") (pintype "power_in"))
      (node (ref "LED64") (pin "2") (pinfunction "GND_2") (pintype "power_in"))
      (node (ref "LED65") (pin "2") (pinfunction "GND_2") (pintype "power_in"))
      (node (ref "LED66") (pin "2") (pinfunction "GND_2") (pintype "power_in"))
      (node (ref "LED67") (pin "2") (pinfunction "GND_2") (pintype "power_in"))
      (node (ref "LED68") (pin "2") (pinfunction "GND_2") (pintype "power_in"))
      (node (ref "LED69") (pin "2") (pinfunction "GND_2") (pintype "power_in"))
      (node (ref "LED7") (pin "2") (pinfunction "GND_2") (pintype "power_in"))
      (node (ref "LED70") (pin "2") (pinfunction "GND_2") (pintype "power_in"))
      (node (ref "LED71") (pin "2") (pinfunction "GND_2") (pintype "power_in"))
      (node (ref "LED72") (pin "2") (pinfunction "GND_2") (pintype "power_in"))
      (node (ref "LED73") (pin "2") (pinfunction "GND_2") (pintype "power_in"))
      (node (ref "LED74") (pin "2") (pinfunction "GND_2") (pintype "power_in"))
      (node (ref "LED75") (pin "2") (pinfunction "GND_2") (pintype "power_in"))
      (node (ref "LED76") (pin "2") (pinfunction "GND_2") (pintype "power_in"))
      (node (ref "LED77") (pin "2") (pinfunction "GND_2") (pintype "power_in"))
      (node (ref "LED78") (pin "2") (pinfunction "GND_2") (pintype "power_in"))
      (node (ref "LED79") (pin "2") (pinfunction "GND_2") (pintype "power_in"))
      (node (ref "LED8") (pin "2") (pinfunction "GND_2") (pintype "power_in"))
      (node (ref "LED80") (pin "2") (pinfunction "GND_2") (pintype "power_in"))
      (node (ref "LED9") (pin "2") (pinfunction "GND_2") (pintype "power_in"))
    )
    (net (code "6") (name "Net-(LED1-DO)") (class "Default")
      (node (ref "LED1") (pin "1") (pinfunction "DO_1") (pintype "output"))
      (node (ref "LED2") (pin "3") (pinfunction "DI_3") (pintype "input"))
    )
    (net (code "7") (name "Net-(LED2-DO)") (class "Default")
      (node (ref "LED2") (pin "1") (pinfunction "DO_1") (pintype "output"))
      (node (ref "LED3") (pin "3") (pinfunction "DI_3") (pintype "input"))
    )
    (net (code "8") (name "Net-(LED3-DO)") (class "Default")
      (node (ref "LED3") (pin "1") (pinfunction "DO_1") (pintype "output"))
      (node (ref "LED4") (pin "3") (pinfunction "DI_3") (pintype "input"))
    )
    (net (code "9") (name "Net-(LED4-DO)") (class "Default")
      (node (ref "LED4") (pin "1") (pinfunction "DO_1") (pintype "output"))
      (node (ref "LED5") (pin "3") (pinfunction "DI_3") (pintype "input"))
    )
    (net (code "10") (name "Net-(LED5-DO)") (class "Default")
      (node (ref "LED5") (pin "1") (pinfunction "DO_1") (pintype "output"))
      (node (ref "LED6") (pin "3") (pinfunction "DI_3") (pintype "input"))
    )
    (net (code "11") (name "Net-(LED6-DO)") (class "Default")
      (node (ref "LED6") (pin "1") (pinfunction "DO_1") (pintype "output"))
      (node (ref "LED7") (pin "3") (pinfunction "DI_3") (pintype "input"))
    )
    (net (code "12") (name "Net-(LED7-DO)") (class "Default")
      (node (ref "LED7") (pin "1") (pinfunction "DO_1") (pintype "output"))
      (node (ref "LED8") (pin "3") (pinfunction "DI_3") (pintype "input"))
    )
    (net (code "13") (name "Net-(LED8-DO)") (class "Default")
      (node (ref "LED8") (pin "1") (pinfunction "DO_1") (pintype "output"))
      (node (ref "LED9") (pin "3") (pinfunction "DI_3") (pintype "input"))
    )
    (net (code "14") (name "Net-(LED10-DI)") (class "Default")
      (node (ref "LED10") (pin "3") (pinfunction "DI_3") (pintype "input"))
      (node (ref "LED9") (pin "1") (pinfunction "DO_1") (pintype "output"))
    )
    (net (code "15") (name "Net-(LED10-DO)") (class "Default")
      (node (ref "LED10") (pin "1") (pinfunction "DO_1") (pintype "output"))
      (node (ref "LED11") (pin "3") (pinfunction "DI_3") (pintype "input"))
    )
    (net (code "16") (name "Net-(LED11-DO)") (class "Default")
      (node (ref "LED11") (pin "1") (pinfunction "DO_1") (pintype "output"))
      (node (ref "LED12") (pin "3") (pinfunction "DI_3") (pintype "input"))
    )
    (net (code "17") (name "Net-(LED12-DO)") (class "Default")
      (node (ref "LED12") (pin "1") (pinfunction "DO_1") (pintype "output"))
      (node (ref "LED13") (pin "3") (pinfunction "DI_3") (pintype "input"))
    )
    (net (code "18") (name "Net-(LED13-DO)") (class "Default")
      (node (ref "LED13") (pin "1") (pinfunction "DO_1") (pintype "output"))
      (node (ref "LED14") (pin "3") (pinfunction "DI_3") (pintype "input"))
    )
    (net (code "19") (name "Net-(LED14-DO)") (class "Default")
      (node (ref "LED14") (pin "1") (pinfunction "DO_1") (pintype "output"))
      (node (ref "LED15") (pin "3") (pinfunction "DI_3") (pintype "input"))
    )
    (net (code "20") (name "Net-(LED15-DO)") (class "Default")
      (node (ref "LED15") (pin "1") (pinfunction "DO_1") (pintype "output"))
      (node (ref "LED16") (pin "3") (pinfunction "DI_3") (pintype "input"))
    )
    (net (code "21") (name "Net-(LED16-DO)") (class "Default")
      (node (ref "LED16") (pin "1") (pinfunction "DO_1") (pintype "output"))
      (node (ref "LED17") (pin "3") (pinfunction "DI_3") (pintype "input"))
    )
    (net (code "22") (name "Net-(LED17-DO)") (class "Default")
      (node (ref "LED17") (pin "1") (pinfunction "DO_1") (pintype "output"))
      (node (ref "LED18") (pin "3") (pinfunction "DI_3") (pintype "input"))
    )
    (net (code "23") (name "Net-(LED18-DO)") (class "Default")
      (node (ref "LED18") (pin "1") (pinfunction "DO_1") (pintype "output"))
      (node (ref "LED19") (pin "3") (pinfunction "DI_3") (pintype "input"))
    )
    (net (code "24") (name "Net-(LED19-DO)") (class "Default")
      (node (ref "LED19") (pin "1") (pinfunction "DO_1") (pintype "output"))
      (node (ref "LED20") (pin "3") (pinfunction "DI_3") (pintype "input"))
    )
    (net (code "25") (name "Net-(LED20-DO)") (class "Default")
      (node (ref "LED20") (pin "1") (pinfunction "DO_1") (pintype "output"))
      (node (ref "LED21") (pin "3") (pinfunction "DI_3") (pintype "input"))
    )
    (net (code "26") (name "Net-(LED21-DO)") (class "Default")
      (node (ref "LED21") (pin "1") (pinfunction "DO_1") (pintype "output"))
      (node (ref "LED22") (pin "3") (pinfunction "DI_3") (pintype "input"))
    )
    (net (code "27") (name "Net-(LED22-DO)") (class "Default")
      (node (ref "LED22") (pin "1") (pinfunction "DO_1") (pintype "output"))
      (node (ref "LED23") (pin "3") (pinfunction "DI_3") (pintype "input"))
    )
    (net (code "28") (name "Net-(LED23-DO)") (class "Default")
      (node (ref "LED23") (pin "1") (pinfunction "DO_1") (pintype "output"))
      (node (ref "LED24") (pin "3") (pinfunction "DI_3") (pintype "input"))
    )
    (net (code "29") (name "Net-(LED24-DO)") (class "Default")
      (node (ref "LED24") (pin "1") (pinfunction "DO_1") (pintype "output"))
      (node (ref "LED25") (pin "3") (pinfunction "DI_3") (pintype "input"))
    )
    (net (code "30") (name "Net-(LED25-DO)") (class "Default")
      (node (ref "LED25") (pin "1") (pinfunction "DO_1") (pintype "output"))
      (node (ref "LED26") (pin "3") (pinfunction "DI_3") (pintype "input"))
    )
    (net (code "31") (name "Net-(LED26-DO)") (class "Default")
      (node (ref "LED26") (pin "1") (pinfunction "DO_1") (pintype "output"))
      (node (ref "LED27") (pin "3") (pinfunction "DI_3") (pintype "input"))
    )
    (net (code "32") (name "Net-(LED27-DO)") (class "Default")
      (node (ref "LED27") (pin "1") (pinfunction "DO_1") (pintype "output"))
      (node (ref "LED28") (pin "3") (pinfunction "DI_3") (pintype "input"))
    )
    (net (code "33") (name "Net-(LED28-DO)") (class "Default")
      (node (ref "LED28") (pin "1") (pinfunction "DO_1") (pintype "output"))
      (node (ref "LED29") (pin "3") (pinfunction "DI_3") (pintype "input"))
    )
    (net (code "34") (name "Net-(LED29-DO)") (class "Default")
      (node (ref "LED29") (pin "1") (pinfunction "DO_1") (pintype "output"))
      (node (ref "LED30") (pin "3") (pinfunction "DI_3") (pintype "input"))
    )
    (net (code "35") (name "Net-(LED30-DO)") (class "Default")
      (node (ref "LED30") (pin "1") (pinfunction "DO_1") (pintype "output"))
      (node (ref "LED31") (pin "3") (pinfunction "DI_3") (pintype "input"))
    )
    (net (code "36") (name "Net-(LED31-DO)") (class "Default")
      (node (ref "LED31") (pin "1") (pinfunction "DO_1") (pintype "output"))
      (node (ref "LED32") (pin "3") (pinfunction "DI_3") (pintype "input"))
    )
    (net (code "37") (name "Net-(LED32-DO)") (class "Default")
      (node (ref "LED32") (pin "1") (pinfunction "DO_1") (pintype "output"))
      (node (ref "LED33") (pin "3") (pinfunction "DI_3") (pintype "input"))
    )
    (net (code "38") (name "Net-(LED33-DO)") (class "Default")
      (node (ref "LED33") (pin "1") (pinfunction "DO_1") (pintype "output"))
      (node (ref "LED34") (pin "3") (pinfunction "DI_3") (pintype "input"))
    )
    (net (code "39") (name "Net-(LED34-DO)") (class "Default")
      (node (ref "LED34") (pin "1") (pinfunction "DO_1") (pintype "output"))
      (node (ref "LED35") (pin "3") (pinfunction "DI_3") (pintype "input"))
    )
    (net (code "40") (name "Net-(LED35-DO)") (class "Default")
      (node (ref "LED35") (pin "1") (pinfunction "DO_1") (pintype "output"))
      (node (ref "LED36") (pin "3") (pinfunction "DI_3") (pintype "input"))
    )
    (net (code "41") (name "Net-(LED36-DO)") (class "Default")
      (node (ref "LED36") (pin "1") (pinfunction "DO_1") (pintype "output"))
      (node (ref "LED37") (pin "3") (pinfunction "DI_3") (pintype "input"))
    )
    (net (code "42") (name "Net-(LED37-DO)") (class "Default")
      (node (ref "LED37") (pin "1") (pinfunction "DO_1") (pintype "output"))
      (node (ref "LED38") (pin "3") (pinfunction "DI_3") (pintype "input"))
    )
    (net (code "43") (name "Net-(LED38-DO)") (class "Default")
      (node (ref "LED38") (pin "1") (pinfunction "DO_1") (pintype "output"))
      (node (ref "LED39") (pin "3") (pinfunction "DI_3") (pintype "input"))
    )
    (net (code "44") (name "Net-(LED39-DO)") (class "Default")
      (node (ref "LED39") (pin "1") (pinfunction "DO_1") (pintype "output"))
      (node (ref "LED40") (pin "3") (pinfunction "DI_3") (pintype "input"))
    )
    (net (code "45") (name "Net-(LED41-DO)") (class "Default")
      (node (ref "LED41") (pin "1") (pinfunction "DO_1") (pintype "output"))
      (node (ref "LED42") (pin "3") (pinfunction "DI_3") (pintype "input"))
    )
    (net (code "46") (name "Net-(LED42-DO)") (class "Default")
      (node (ref "LED42") (pin "1") (pinfunction "DO_1") (pintype "output"))
      (node (ref "LED43") (pin "3") (pinfunction "DI_3") (pintype "input"))
    )
    (net (code "47") (name "Net-(LED43-DO)") (class "Default")
      (node (ref "LED43") (pin "1") (pinfunction "DO_1") (pintype "output"))
      (node (ref "LED44") (pin "3") (pinfunction "DI_3") (pintype "input"))
    )
    (net (code "48") (name "Net-(LED44-DO)") (class "Default")
      (node (ref "LED44") (pin "1") (pinfunction "DO_1") (pintype "output"))
      (node (ref "LED45") (pin "3") (pinfunction "DI_3") (pintype "input"))
    )
    (net (code "49") (name "Net-(LED45-DO)") (class "Default")
      (node (ref "LED45") (pin "1") (pinfunction "DO_1") (pintype "output"))
      (node (ref "LED46") (pin "3") (pinfunction "DI_3") (pintype "input"))
    )
    (net (code "50") (name "Net-(LED46-DO)") (class "Default")
      (node (ref "LED46") (pin "1") (pinfunction "DO_1") (pintype "output"))
      (node (ref "LED47") (pin "3") (pinfunction "DI_3") (pintype "input"))
    )
    (net (code "51") (name "Net-(LED47-DO)") (class "Default")
      (node (ref "LED47") (pin "1") (pinfunction "DO_1") (pintype "output"))
      (node (ref "LED48") (pin "3") (pinfunction "DI_3") (pintype "input"))
    )
    (net (code "52") (name "Net-(LED48-DO)") (class "Default")
      (node (ref "LED48") (pin "1") (pinfunction "DO_1") (pintype "output"))
      (node (ref "LED49") (pin "3") (pinfunction "DI_3") (pintype "input"))
    )
    (net (code "53") (name "Net-(LED49-DO)") (class "Default")
      (node (ref "LED49") (pin "1") (pinfunction "DO_1") (pintype "output"))
      (node (ref "LED50") (pin "3") (pinfunction "DI_3") (pintype "input"))
    )
    (net (code "54") (name "Net-(LED50-DO)") (class "Default")
      (node (ref "LED50") (pin "1") (pinfunction "DO_1") (pintype "output"))
      (node (ref "LED51") (pin "3") (pinfunction "DI_3") (pintype "input"))
    )
    (net (code "55") (name "Net-(LED51-DO)") (class "Default")
      (node (ref "LED51") (pin "1") (pinfunction "DO_1") (pintype "output"))
      (node (ref "LED52") (pin "3") (pinfunction "DI_3") (pintype "input"))
    )
    (net (code "56") (name "Net-(LED52-DO)") (class "Default")
      (node (ref "LED52") (pin "1") (pinfunction "DO_1") (pintype "output"))
      (node (ref "LED53") (pin "3") (pinfunction "DI_3") (pintype "input"))
    )
    (net (code "57") (name "Net-(LED53-DO)") (class "Default")
      (node (ref "LED53") (pin "1") (pinfunction "DO_1") (pintype "output"))
      (node (ref "LED54") (pin "3") (pinfunction "DI_3") (pintype "input"))
    )
    (net (code "58") (name "Net-(LED54-DO)") (class "Default")
      (node (ref "LED54") (pin "1") (pinfunction "DO_1") (pintype "output"))
      (node (ref "LED55") (pin "3") (pinfunction "DI_3") (pintype "input"))
    )
    (net (code "59") (name "Net-(LED55-DO)") (class "Default")
      (node (ref "LED55") (pin "1") (pinfunction "DO_1") (pintype "output"))
      (node (ref "LED56") (pin "3") (pinfunction "DI_3") (pintype "input"))
    )
    (net (code "60") (name "Net-(LED56-DO)") (class "Default")
      (node (ref "LED56") (pin "1") (pinfunction "DO_1") (pintype "output"))
      (node (ref "LED57") (pin "3") (pinfunction "DI_3") (pintype "input"))
    )
    (net (code "61") (name "Net-(LED57-DO)") (class "Default")
      (node (ref "LED57") (pin "1") (pinfunction "DO_1") (pintype "output"))
      (node (ref "LED58") (pin "3") (pinfunction "DI_3") (pintype "input"))
    )
    (net (code "62") (name "Net-(LED58-DO)") (class "Default")
      (node (ref "LED58") (pin "1") (pinfunction "DO_1") (pintype "output"))
      (node (ref "LED59") (pin "3") (pinfunction "DI_3") (pintype "input"))
    )
    (net (code "63") (name "Net-(LED59-DO)") (class "Default")
      (node (ref "LED59") (pin "1") (pinfunction "DO_1") (pintype "output"))
      (node (ref "LED60") (pin "3") (pinfunction "DI_3") (pintype "input"))
    )
    (net (code "64") (name "Net-(LED60-DO)") (class "Default")
      (node (ref "LED60") (pin "1") (pinfunction "DO_1") (pintype "output"))
      (node (ref "LED61") (pin "3") (pinfunction "DI_3") (pintype "input"))
    )
    (net (code "65") (name "Net-(LED61-DO)") (class "Default")
      (node (ref "LED61") (pin "1") (pinfunction "DO_1") (pintype "output"))
      (node (ref "LED62") (pin "3") (pinfunction "DI_3") (pintype "input"))
    )
    (net (code "66") (name "Net-(LED62-DO)") (class "Default")
      (node (ref "LED62") (pin "1") (pinfunction "DO_1") (pintype "output"))
      (node (ref "LED63") (pin "3") (pinfunction "DI_3") (pintype "input"))
    )
    (net (code "67") (name "Net-(LED63-DO)") (class "Default")
      (node (ref "LED63") (pin "1") (pinfunction "DO_1") (pintype "output"))
      (node (ref "LED64") (pin "3") (pinfunction "DI_3") (pintype "input"))
    )
    (net (code "68") (name "Net-(LED64-DO)") (class "Default")
      (node (ref "LED64") (pin "1") (pinfunction "DO_1") (pintype "output"))
      (node (ref "LED65") (pin "3") (pinfunction "DI_3") (pintype "input"))
    )
    (net (code "69") (name "Net-(LED65-DO)") (class "Default")
      (node (ref "LED65") (pin "1") (pinfunction "DO_1") (pintype "output"))
      (node (ref "LED66") (pin "3") (pinfunction "DI_3") (pintype "input"))
    )
    (net (code "70") (name "Net-(LED66-DO)") (class "Default")
      (node (ref "LED66") (pin "1") (pinfunction "DO_1") (pintype "output"))
      (node (ref "LED67") (pin "3") (pinfunction "DI_3") (pintype "input"))
    )
    (net (code "71") (name "Net-(LED67-DO)") (class "Default")
      (node (ref "LED67") (pin "1") (pinfunction "DO_1") (pintype "output"))
      (node (ref "LED68") (pin "3") (pinfunction "DI_3") (pintype "input"))
    )
    (net (code "72") (name "Net-(LED68-DO)") (class "Default")
      (node (ref "LED68") (pin "1") (pinfunction "DO_1") (pintype "output"))
      (node (ref "LED69") (pin "3") (pinfunction "DI_3") (pintype "input"))
    )
    (net (code "73") (name "Net-(LED69-DO)") (class "Default")
      (node (ref "LED69") (pin "1") (pinfunction "DO_1") (pintype "output"))
      (node (ref "LED70") (pin "3") (pinfunction "DI_3") (pintype "input"))
    )
    (net (code "74") (name "Net-(LED70-DO)") (class "Default")
      (node (ref "LED70") (pin "1") (pinfunction "DO_1") (pintype "output"))
      (node (ref "LED71") (pin "3") (pinfunction "DI_3") (pintype "input"))
    )
    (net (code "75") (name "Net-(LED71-DO)") (class "Default")
      (node (ref "LED71") (pin "1") (pinfunction "DO_1") (pintype "output"))
      (node (ref "LED72") (pin "3") (pinfunction "DI_3") (pintype "input"))
    )
    (net (code "76") (name "Net-(LED72-DO)") (class "Default")
      (node (ref "LED72") (pin "1") (pinfunction "DO_1") (pintype "output"))
      (node (ref "LED73") (pin "3") (pinfunction "DI_3") (pintype "input"))
    )
    (net (code "77") (name "Net-(LED73-DO)") (class "Default")
      (node (ref "LED73") (pin "1") (pinfunction "DO_1") (pintype "output"))
      (node (ref "LED74") (pin "3") (pinfunction "DI_3") (pintype "input"))
    )
    (net (code "78") (name "Net-(LED74-DO)") (class "Default")
      (node (ref "LED74") (pin "1") (pinfunction "DO_1") (pintype "output"))
      (node (ref "LED75") (pin "3") (pinfunction "DI_3") (pintype "input"))
    )
    (net (code "79") (name "Net-(LED75-DO)") (class "Default")
      (node (ref "LED75") (pin "1") (pinfunction "DO_1") (pintype "output"))
      (node (ref "LED76") (pin "3") (pinfunction "DI_3") (pintype "input"))
    )
    (net (code "80") (name "Net-(LED76-DO)") (class "Default")
      (node (ref "LED76") (pin "1") (pinfunction "DO_1") (pintype "output"))
      (node (ref "LED77") (pin "3") (pinfunction "DI_3") (pintype "input"))
    )
    (net (code "81") (name "Net-(LED77-DO)") (class "Default")
      (node (ref "LED77") (pin "1") (pinfunction "DO_1") (pintype "output"))
      (node (ref "LED78") (pin "3") (pinfunction "DI_3") (pintype "input"))
    )
    (net (code "82") (name "Net-(LED78-DO)") (class "Default")
      (node (ref "LED78") (pin "1") (pinfunction "DO_1") (pintype "output"))
      (node (ref "LED79") (pin "3") (pinfunction "DI_3") (pintype "input"))
    )
    (net (code "83") (name "Net-(LED79-DO)") (class "Default")
      (node (ref "LED79") (pin "1") (pinfunction "DO_1") (pintype "output"))
      (node (ref "LED80") (pin "3") (pinfunction "DI_3") (pintype "input"))
    )
    (net (code "84") (name "unconnected-(J4-Pad4)") (class "Default")
      (node (ref "J4") (pin "4") (pinfunction "4_4") (pintype "passive"))
    )
    (net (code "85") (name "unconnected-(J5-Pad4)") (class "Default")
      (node (ref "J5") (pin "4") (pinfunction "4_4") (pintype "passive"))
    )
  )
)
